# Tarea1.net
KiCad netlist of a schematic drawn in EAGLE
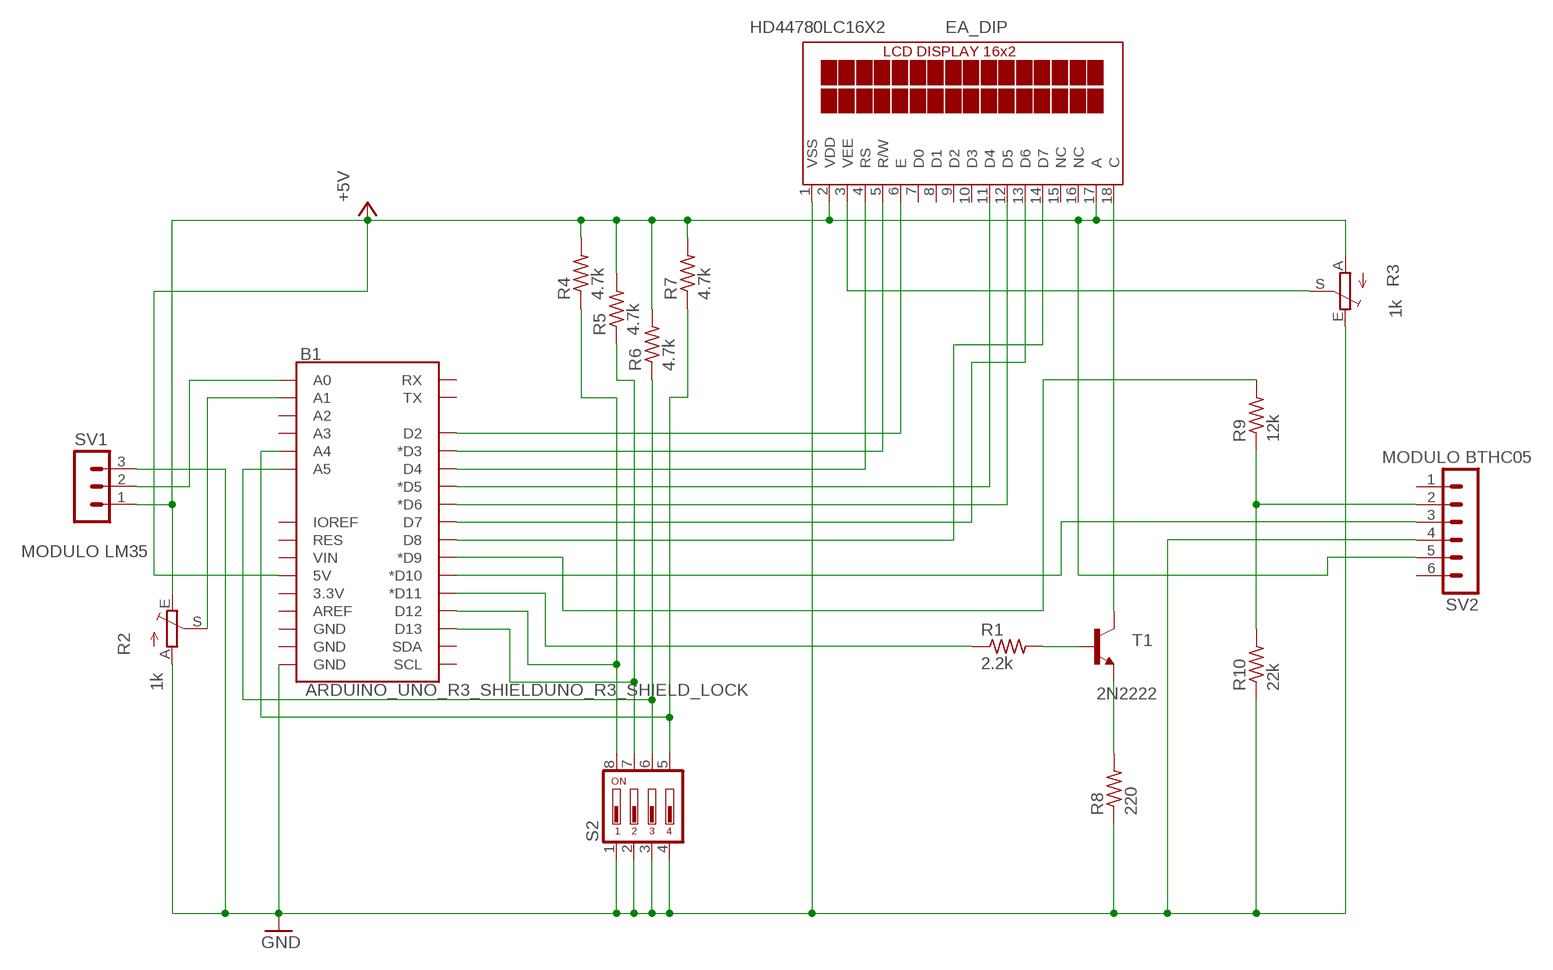
[diagram p0: schematic, sheet 1]

(export (version "E")
  (design (tool "Eeschema 10.0.6"))
  (components
    (comp (ref "B1")
      (value "ARDUINO_UNO_R3_SHIELDUNO_R3_SHIELD_LOCK")
      (footprint "eagle-import:UNO_R3_SHIELD_LOCK")
      (libsource (lib "eagle-import") (part "ARDUINO_UNO_R3_SHIELDUNO_R3_SHIELD_LOCK"))
    )
    (comp (ref "HD44780LC16X2")
      (value "EA_DIP")
      (footprint "eagle-import:EA_DIP")
      (libsource (lib "eagle-import") (part "EA_DIP"))
    )
    (comp (ref "R1")
      (value "2.2k")
      (footprint "eagle-import:0207_10")
      (libsource (lib "eagle-import") (part "R-US_0207/10"))
    )
    (comp (ref "R2")
      (value "1k")
      (footprint "eagle-import:B25P")
      (libsource (lib "eagle-import") (part "TRIM_EU-B25P"))
    )
    (comp (ref "R3")
      (value "1k")
      (footprint "eagle-import:B25P")
      (libsource (lib "eagle-import") (part "TRIM_EU-B25P"))
    )
    (comp (ref "R4")
      (value "4.7k")
      (footprint "eagle-import:0207_10")
      (libsource (lib "eagle-import") (part "R-US_0207/10"))
    )
    (comp (ref "R5")
      (value "4.7k")
      (footprint "eagle-import:0207_10")
      (libsource (lib "eagle-import") (part "R-US_0207/10"))
    )
    (comp (ref "R6")
      (value "4.7k")
      (footprint "eagle-import:0207_10")
      (libsource (lib "eagle-import") (part "R-US_0207/10"))
    )
    (comp (ref "R7")
      (value "4.7k")
      (footprint "eagle-import:0207_10")
      (libsource (lib "eagle-import") (part "R-US_0207/10"))
    )
    (comp (ref "R8")
      (value "220")
      (footprint "eagle-import:0207_10")
      (libsource (lib "eagle-import") (part "R-US_0207/10"))
    )
    (comp (ref "R9")
      (value "12k")
      (footprint "eagle-import:0207_10")
      (libsource (lib "eagle-import") (part "R-US_0207/10"))
    )
    (comp (ref "R10")
      (value "22k")
      (footprint "eagle-import:0207_10")
      (libsource (lib "eagle-import") (part "R-US_0207/10"))
    )
    (comp (ref "S2")
      (value "SD4-04")
      (footprint "eagle-import:SD4-04")
      (libsource (lib "eagle-import") (part "SD4-04"))
    )
    (comp (ref "SV1")
      (value "MODULO LM35")
      (footprint "eagle-import:MA03-1")
      (libsource (lib "eagle-import") (part "MA03-1"))
    )
    (comp (ref "SV2")
      (value "MODULO BTHC05")
      (footprint "eagle-import:MA06-1")
      (libsource (lib "eagle-import") (part "MA06-1"))
    )
    (comp (ref "T1")
      (value "2N2222")
      (footprint "eagle-import:TO18")
      (libsource (lib "eagle-import") (part "2N2222"))
    )
  )
  (nets
    (net (code "1") (name "+5V") (class "Default")
      (node (ref "B1") (pin "5V") (pinfunction "5V_5V") (pintype "bidirectional"))
      (node (ref "HD44780LC16X2") (pin "17") (pinfunction "A_17") (pintype "passive"))
      (node (ref "HD44780LC16X2") (pin "2") (pinfunction "VDD_2") (pintype "power_in"))
      (node (ref "R2") (pin "E") (pinfunction "E_E") (pintype "passive"))
      (node (ref "R3") (pin "A") (pinfunction "A_A") (pintype "passive"))
      (node (ref "R4") (pin "2") (pinfunction "2_2") (pintype "passive"))
      (node (ref "R5") (pin "2") (pinfunction "2_2") (pintype "passive"))
      (node (ref "R6") (pin "2") (pinfunction "2_2") (pintype "passive"))
      (node (ref "R7") (pin "2") (pinfunction "2_2") (pintype "passive"))
      (node (ref "SV1") (pin "1") (pinfunction "1_1") (pintype "passive"))
      (node (ref "SV2") (pin "5") (pinfunction "5_5") (pintype "passive"))
    )
    (net (code "2") (name "GND") (class "Default")
      (node (ref "B1") (pin "GND@0") (pinfunction "GND_GND@0") (pintype "bidirectional"))
      (node (ref "HD44780LC16X2") (pin "1") (pinfunction "VSS_1") (pintype "power_in"))
      (node (ref "R10") (pin "1") (pinfunction "1_1") (pintype "passive"))
      (node (ref "R2") (pin "A") (pinfunction "A_A") (pintype "passive"))
      (node (ref "R3") (pin "E") (pinfunction "E_E") (pintype "passive"))
      (node (ref "R8") (pin "1") (pinfunction "1_1") (pintype "passive"))
      (node (ref "S2") (pin "1") (pinfunction "1_1") (pintype "passive"))
      (node (ref "S2") (pin "2") (pinfunction "2_2") (pintype "passive"))
      (node (ref "S2") (pin "3") (pinfunction "3_3") (pintype "passive"))
      (node (ref "S2") (pin "4") (pinfunction "4_4") (pintype "passive"))
      (node (ref "SV1") (pin "3") (pinfunction "3_3") (pintype "passive"))
      (node (ref "SV2") (pin "4") (pinfunction "4_4") (pintype "passive"))
    )
    (net (code "3") (name "Net-(B1-*D3)") (class "Default")
      (node (ref "B1") (pin "D3") (pinfunction "*D3_D3") (pintype "bidirectional"))
      (node (ref "HD44780LC16X2") (pin "5") (pinfunction "R/W_5") (pintype "input"))
    )
    (net (code "4") (name "Net-(B1-*D5)") (class "Default")
      (node (ref "B1") (pin "D5") (pinfunction "*D5_D5") (pintype "bidirectional"))
      (node (ref "HD44780LC16X2") (pin "11") (pinfunction "D4_11") (pintype "input"))
    )
    (net (code "5") (name "Net-(B1-*D6)") (class "Default")
      (node (ref "B1") (pin "D6") (pinfunction "*D6_D6") (pintype "bidirectional"))
      (node (ref "HD44780LC16X2") (pin "12") (pinfunction "D5_12") (pintype "input"))
    )
    (net (code "6") (name "Net-(B1-*D9)") (class "Default")
      (node (ref "B1") (pin "D9") (pinfunction "*D9_D9") (pintype "bidirectional"))
      (node (ref "R9") (pin "2") (pinfunction "2_2") (pintype "passive"))
    )
    (net (code "7") (name "Net-(B1-*D10)") (class "Default")
      (node (ref "B1") (pin "D10") (pinfunction "*D10_D10") (pintype "bidirectional"))
      (node (ref "SV2") (pin "3") (pinfunction "3_3") (pintype "passive"))
    )
    (net (code "8") (name "Net-(B1-*D11)") (class "Default")
      (node (ref "B1") (pin "D11") (pinfunction "*D11_D11") (pintype "bidirectional"))
      (node (ref "R1") (pin "1") (pinfunction "1_1") (pintype "passive"))
    )
    (net (code "9") (name "Net-(B1-PadA0)") (class "Default")
      (node (ref "B1") (pin "A0") (pinfunction "A0_A0") (pintype "bidirectional"))
      (node (ref "SV1") (pin "2") (pinfunction "2_2") (pintype "passive"))
    )
    (net (code "10") (name "Net-(B1-PadA1)") (class "Default")
      (node (ref "B1") (pin "A1") (pinfunction "A1_A1") (pintype "bidirectional"))
      (node (ref "R2") (pin "S") (pinfunction "S_S") (pintype "passive"))
    )
    (net (code "11") (name "Net-(B1-PadA4)") (class "Default")
      (node (ref "B1") (pin "A4") (pinfunction "A4_A4") (pintype "bidirectional"))
      (node (ref "R7") (pin "1") (pinfunction "1_1") (pintype "passive"))
      (node (ref "S2") (pin "5") (pinfunction "5_5") (pintype "passive"))
    )
    (net (code "12") (name "Net-(B1-PadA5)") (class "Default")
      (node (ref "B1") (pin "A5") (pinfunction "A5_A5") (pintype "bidirectional"))
      (node (ref "R6") (pin "1") (pinfunction "1_1") (pintype "passive"))
      (node (ref "S2") (pin "6") (pinfunction "6_6") (pintype "passive"))
    )
    (net (code "13") (name "Net-(B1-PadD12)") (class "Default")
      (node (ref "B1") (pin "D12") (pinfunction "D12_D12") (pintype "bidirectional"))
      (node (ref "R4") (pin "1") (pinfunction "1_1") (pintype "passive"))
      (node (ref "S2") (pin "8") (pinfunction "8_8") (pintype "passive"))
    )
    (net (code "14") (name "Net-(B1-PadD13)") (class "Default")
      (node (ref "B1") (pin "D13") (pinfunction "D13_D13") (pintype "bidirectional"))
      (node (ref "R5") (pin "1") (pinfunction "1_1") (pintype "passive"))
      (node (ref "S2") (pin "7") (pinfunction "7_7") (pintype "passive"))
    )
    (net (code "15") (name "Net-(HD44780LC16X2-C)") (class "Default")
      (node (ref "HD44780LC16X2") (pin "18") (pinfunction "C_18") (pintype "passive"))
      (node (ref "T1") (pin "3") (pinfunction "C_3") (pintype "passive"))
    )
    (net (code "16") (name "Net-(HD44780LC16X2-D6)") (class "Default")
      (node (ref "B1") (pin "D7") (pinfunction "D7_D7") (pintype "bidirectional"))
      (node (ref "HD44780LC16X2") (pin "13") (pinfunction "D6_13") (pintype "input"))
    )
    (net (code "17") (name "Net-(HD44780LC16X2-D7)") (class "Default")
      (node (ref "B1") (pin "D8") (pinfunction "D8_D8") (pintype "bidirectional"))
      (node (ref "HD44780LC16X2") (pin "14") (pinfunction "D7_14") (pintype "input"))
    )
    (net (code "18") (name "Net-(HD44780LC16X2-E)") (class "Default")
      (node (ref "B1") (pin "D2") (pinfunction "D2_D2") (pintype "bidirectional"))
      (node (ref "HD44780LC16X2") (pin "6") (pinfunction "E_6") (pintype "input"))
    )
    (net (code "19") (name "Net-(HD44780LC16X2-RS)") (class "Default")
      (node (ref "B1") (pin "D4") (pinfunction "D4_D4") (pintype "bidirectional"))
      (node (ref "HD44780LC16X2") (pin "4") (pinfunction "RS_4") (pintype "input"))
    )
    (net (code "20") (name "Net-(HD44780LC16X2-VEE)") (class "Default")
      (node (ref "HD44780LC16X2") (pin "3") (pinfunction "VEE_3") (pintype "power_in"))
      (node (ref "R3") (pin "S") (pinfunction "S_S") (pintype "passive"))
    )
    (net (code "21") (name "Net-(R10-Pad2)") (class "Default")
      (node (ref "R10") (pin "2") (pinfunction "2_2") (pintype "passive"))
      (node (ref "R9") (pin "1") (pinfunction "1_1") (pintype "passive"))
      (node (ref "SV2") (pin "2") (pinfunction "2_2") (pintype "passive"))
    )
    (net (code "22") (name "Net-(T1-B)") (class "Default")
      (node (ref "R1") (pin "2") (pinfunction "2_2") (pintype "passive"))
      (node (ref "T1") (pin "2") (pinfunction "B_2") (pintype "passive"))
    )
    (net (code "23") (name "Net-(T1-E)") (class "Default")
      (node (ref "R8") (pin "2") (pinfunction "2_2") (pintype "passive"))
      (node (ref "T1") (pin "1") (pinfunction "E_1") (pintype "passive"))
    )
    (net (code "24") (name "unconnected-(B1-GND-PadGND@1)") (class "Default")
      (node (ref "B1") (pin "GND@1") (pinfunction "GND_GND@1") (pintype "bidirectional"))
    )
    (net (code "25") (name "unconnected-(B1-GND-PadGND@2)") (class "Default")
      (node (ref "B1") (pin "GND@2") (pinfunction "GND_GND@2") (pintype "bidirectional"))
    )
    (net (code "26") (name "unconnected-(B1-Pad3.3V)") (class "Default")
      (node (ref "B1") (pin "3.3V") (pinfunction "3.3V_3.3V") (pintype "bidirectional"))
    )
    (net (code "27") (name "unconnected-(B1-PadA2)") (class "Default")
      (node (ref "B1") (pin "A2") (pinfunction "A2_A2") (pintype "bidirectional"))
    )
    (net (code "28") (name "unconnected-(B1-PadA3)") (class "Default")
      (node (ref "B1") (pin "A3") (pinfunction "A3_A3") (pintype "bidirectional"))
    )
    (net (code "29") (name "unconnected-(B1-PadAREF)") (class "Default")
      (node (ref "B1") (pin "AREF") (pinfunction "AREF_AREF") (pintype "bidirectional"))
    )
    (net (code "30") (name "unconnected-(B1-PadIOREF)") (class "Default")
      (node (ref "B1") (pin "IOREF") (pinfunction "IOREF_IOREF") (pintype "bidirectional"))
    )
    (net (code "31") (name "unconnected-(B1-PadRES)") (class "Default")
      (node (ref "B1") (pin "RES") (pinfunction "RES_RES") (pintype "bidirectional"))
    )
    (net (code "32") (name "unconnected-(B1-PadRX)") (class "Default")
      (node (ref "B1") (pin "RX") (pinfunction "RX_RX") (pintype "bidirectional"))
    )
    (net (code "33") (name "unconnected-(B1-PadSCL)") (class "Default")
      (node (ref "B1") (pin "SCL") (pinfunction "SCL_SCL") (pintype "bidirectional"))
    )
    (net (code "34") (name "unconnected-(B1-PadSDA)") (class "Default")
      (node (ref "B1") (pin "SDA") (pinfunction "SDA_SDA") (pintype "bidirectional"))
    )
    (net (code "35") (name "unconnected-(B1-PadTX)") (class "Default")
      (node (ref "B1") (pin "TX") (pinfunction "TX_TX") (pintype "bidirectional"))
    )
    (net (code "36") (name "unconnected-(B1-PadVIN)") (class "Default")
      (node (ref "B1") (pin "VIN") (pinfunction "VIN_VIN") (pintype "bidirectional"))
    )
    (net (code "37") (name "unconnected-(HD44780LC16X2-D0-Pad7)") (class "Default")
      (node (ref "HD44780LC16X2") (pin "7") (pinfunction "D0_7") (pintype "input"))
    )
    (net (code "38") (name "unconnected-(HD44780LC16X2-D1-Pad8)") (class "Default")
      (node (ref "HD44780LC16X2") (pin "8") (pinfunction "D1_8") (pintype "input"))
    )
    (net (code "39") (name "unconnected-(HD44780LC16X2-D2-Pad9)") (class "Default")
      (node (ref "HD44780LC16X2") (pin "9") (pinfunction "D2_9") (pintype "input"))
    )
    (net (code "40") (name "unconnected-(HD44780LC16X2-D3-Pad10)") (class "Default")
      (node (ref "HD44780LC16X2") (pin "10") (pinfunction "D3_10") (pintype "input"))
    )
    (net (code "41") (name "unconnected-(HD44780LC16X2-NC-Pad15)") (class "Default")
      (node (ref "HD44780LC16X2") (pin "15") (pinfunction "NC_15") (pintype "no_connect"))
    )
    (net (code "42") (name "unconnected-(HD44780LC16X2-NC-Pad16)") (class "Default")
      (node (ref "HD44780LC16X2") (pin "16") (pinfunction "NC_16") (pintype "no_connect"))
    )
    (net (code "43") (name "unconnected-(SV2-Pad1)") (class "Default")
      (node (ref "SV2") (pin "1") (pinfunction "1_1") (pintype "passive"))
    )
    (net (code "44") (name "unconnected-(SV2-Pad6)") (class "Default")
      (node (ref "SV2") (pin "6") (pinfunction "6_6") (pintype "passive"))
    )
  )
)
